# Group_5.net
KiCad netlist of a schematic drawn in EAGLE
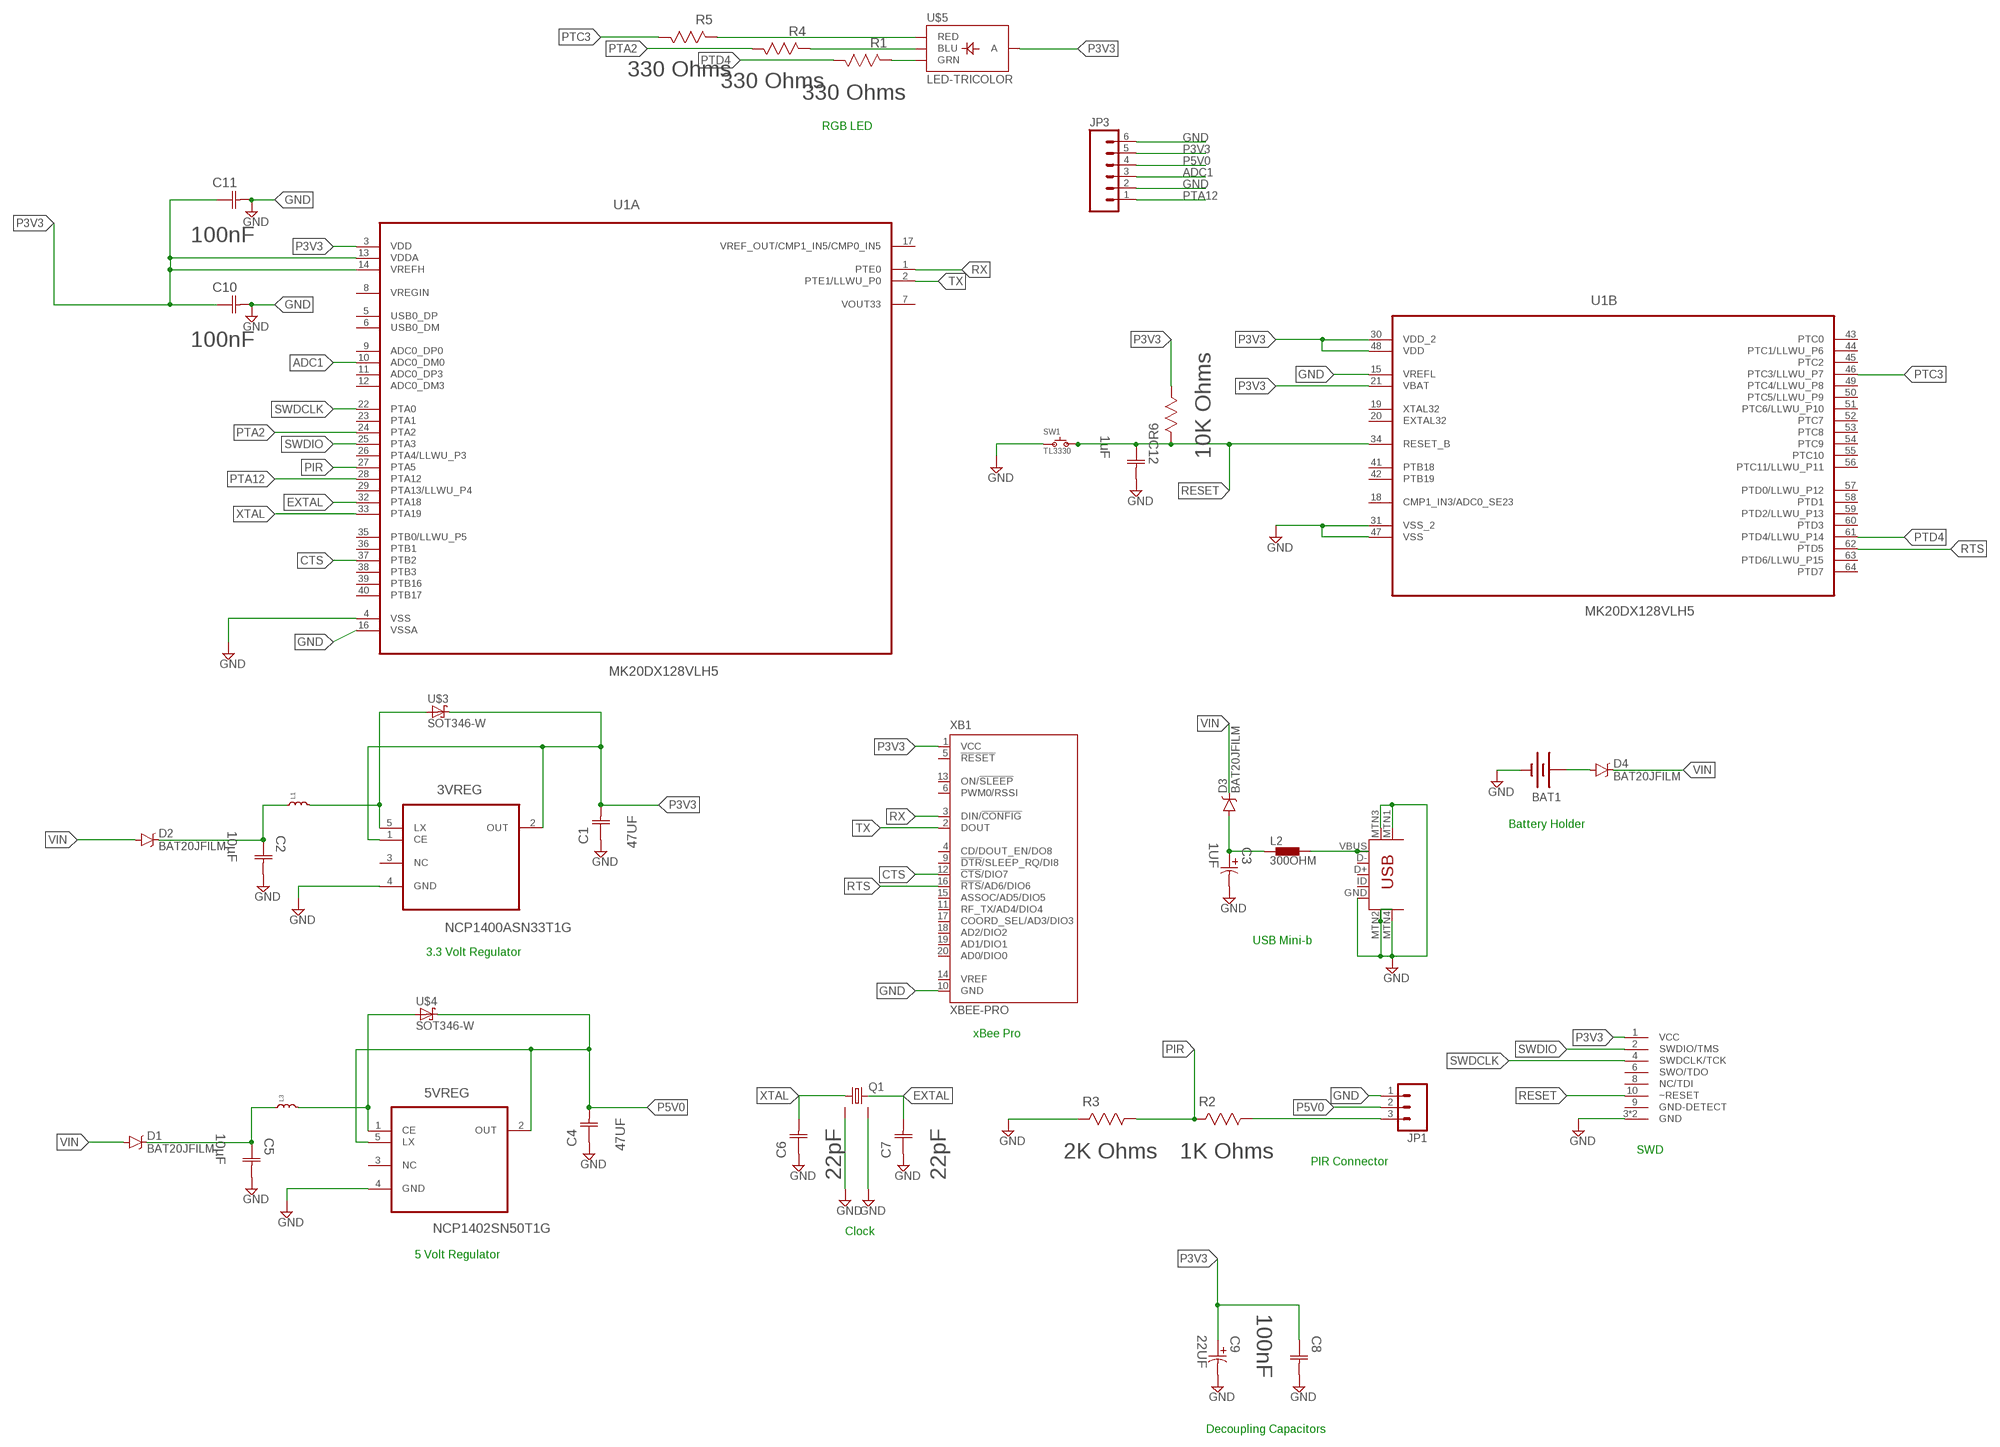
[diagram p0: schematic, sheet 1]

(export (version "E")
  (design (tool "Eeschema 10.0.6"))
  (components
    (comp (ref "3VREG")
      (value "NCP1400ASN33T1G")
      (footprint "eagle-import:SOT95P275X110-5N")
      (libsource (lib "eagle-import") (part "NCP1400ASN33T1G"))
    )
    (comp (ref "5VREG")
      (value "NCP1402SN50T1G")
      (footprint "eagle-import:SOT95P275X110-5N")
      (libsource (lib "eagle-import") (part "NCP1402SN50T1G"))
    )
    (comp (ref "BAT1")
      (value "BATTERY20PTH")
      (footprint "eagle-import:BATTCOM_20MM_PTH")
      (libsource (lib "eagle-import") (part "BATTERY20PTH"))
    )
    (comp (ref "C1")
      (value "47UF")
      (footprint "eagle-import:CAPCP6032X280N")
      (fields (field (name "MPN") "TPSC476M010R0350"))
      (libsource (lib "eagle-import") (part "TPSC476M010R0350"))
    )
    (comp (ref "C2")
      (value "10µF")
      (footprint "eagle-import:CAPCP6032X280N")
      (fields (field (name "MPN") "TAJC106M020R"))
      (libsource (lib "eagle-import") (part "TAJC106M020R"))
    )
    (comp (ref "C3")
      (value "1UF")
      (footprint "eagle-import:CAPAE430X610N")
      (fields (field (name "MPN") "EEE-1HA010SR") (field (name "TOLERANCE") " 20%"))
      (libsource (lib "eagle-import") (part "EEE--CASE-B1HA010SR"))
    )
    (comp (ref "C4")
      (value "47UF")
      (footprint "eagle-import:CAPCP6032X280N")
      (fields (field (name "MPN") "TPSC476M010R0350"))
      (libsource (lib "eagle-import") (part "TPSC476M010R0350"))
    )
    (comp (ref "C5")
      (value "10µF")
      (footprint "eagle-import:CAPCP6032X280N")
      (fields (field (name "MPN") "TAJC106M020R"))
      (libsource (lib "eagle-import") (part "TAJC106M020R"))
    )
    (comp (ref "C6")
      (value "22pF")
      (footprint "eagle-import:CAPC1608X85N")
      (fields (field (name "MPN") "C0603C220J5GACTU") (field (name "TOLERANCE") "±5%"))
      (libsource (lib "eagle-import") (part "C0603C220J5GACTU"))
    )
    (comp (ref "C7")
      (value "22pF")
      (footprint "eagle-import:CAPC1608X85N")
      (fields (field (name "MPN") "C0603C220J5GACTU") (field (name "TOLERANCE") "±5%"))
      (libsource (lib "eagle-import") (part "C0603C220J5GACTU"))
    )
    (comp (ref "C8")
      (value "100nF")
      (footprint "eagle-import:CAPC2013X95N")
      (fields (field (name "MPN") "CC0805KRX7R9BB104") (field (name "TOLERANCE") "±10%"))
      (libsource (lib "eagle-import") (part "CC0805KRX7R9BB104"))
    )
    (comp (ref "C9")
      (value "22UF")
      (footprint "eagle-import:CAPAE430X610N")
      (fields (field (name "MPN") "EEE-FT1V220AR") (field (name "TOLERANCE") "±20 %"))
      (libsource (lib "eagle-import") (part "EEE--CASE-BFT1V220AR"))
    )
    (comp (ref "C10")
      (value "100nF")
      (footprint "eagle-import:CAPC2013X95N")
      (fields (field (name "MPN") "CC0805KRX7R9BB104") (field (name "TOLERANCE") "±10%"))
      (libsource (lib "eagle-import") (part "CC0805KRX7R9BB104"))
    )
    (comp (ref "C11")
      (value "100nF")
      (footprint "eagle-import:CAPC2013X95N")
      (fields (field (name "MPN") "CC0805KRX7R9BB104") (field (name "TOLERANCE") "±10%"))
      (libsource (lib "eagle-import") (part "CC0805KRX7R9BB104"))
    )
    (comp (ref "C12")
      (value "1uF")
      (footprint "eagle-import:CAPC1608X94N")
      (fields (field (name "MPN") "0603YC105KAT2A") (field (name "TOLERANCE") "±10%"))
      (libsource (lib "eagle-import") (part "0603YC105KAT2A"))
    )
    (comp (ref "D1")
      (value "BAT20JFILM")
      (footprint "eagle-import:SOD-323")
      (libsource (lib "eagle-import") (part "BAT20JFILM"))
    )
    (comp (ref "D2")
      (value "BAT20JFILM")
      (footprint "eagle-import:SOD-323")
      (libsource (lib "eagle-import") (part "BAT20JFILM"))
    )
    (comp (ref "D3")
      (value "BAT20JFILM")
      (footprint "eagle-import:SOD-323")
      (libsource (lib "eagle-import") (part "BAT20JFILM"))
    )
    (comp (ref "D4")
      (value "BAT20JFILM")
      (footprint "eagle-import:SOD-323")
      (libsource (lib "eagle-import") (part "BAT20JFILM"))
    )
    (comp (ref "JP1")
      (value "M03PTH")
      (footprint "eagle-import:1X03")
      (libsource (lib "eagle-import") (part "M03PTH"))
    )
    (comp (ref "JP3")
      (value "M06LONGPADS")
      (footprint "eagle-import:1X06_LONGPADS")
      (libsource (lib "eagle-import") (part "M06LONGPADS"))
    )
    (comp (ref "L1")
      (value "INDUCTOR-SDR0403")
      (footprint "eagle-import:SDR0403")
      (libsource (lib "eagle-import") (part "INDUCTOR-SDR0403"))
    )
    (comp (ref "L2")
      (value "300OHM")
      (footprint "eagle-import:0402")
      (libsource (lib "eagle-import") (part "BLM15HB121SN1"))
    )
    (comp (ref "L3")
      (value "INDUCTOR-SDR0403")
      (footprint "eagle-import:SDR0403")
      (libsource (lib "eagle-import") (part "INDUCTOR-SDR0403"))
    )
    (comp (ref "Q1")
      (value "CRYSTALCTS406")
      (footprint "eagle-import:CTS406")
      (libsource (lib "eagle-import") (part "CRYSTALCTS406"))
    )
    (comp (ref "R1")
      (value "330 Ohms")
      (footprint "eagle-import:RESC2013X65N")
      (fields (field (name "MPN") "MC0.1W08051%330R") (field (name "TOLERANCE") "±1%"))
      (libsource (lib "eagle-import") (part "MC0.1W08051%330R"))
    )
    (comp (ref "R2")
      (value "1K Ohms")
      (footprint "eagle-import:RESC3216X71N")
      (fields (field (name "MPN") "MC0.125W12061%1K") (field (name "TOLERANCE") "±1%"))
      (libsource (lib "eagle-import") (part "MC0.125W12061%1K"))
    )
    (comp (ref "R3")
      (value "2K Ohms")
      (footprint "eagle-import:RESC3216X71N")
      (fields (field (name "MPN") "MC0.125W12061%2K") (field (name "TOLERANCE") "±1%"))
      (libsource (lib "eagle-import") (part "MC0.125W12061%2K"))
    )
    (comp (ref "R4")
      (value "330 Ohms")
      (footprint "eagle-import:RESC2013X65N")
      (fields (field (name "MPN") "MC0.1W08051%330R") (field (name "TOLERANCE") "±1%"))
      (libsource (lib "eagle-import") (part "MC0.1W08051%330R"))
    )
    (comp (ref "R5")
      (value "330 Ohms")
      (footprint "eagle-import:RESC2013X65N")
      (fields (field (name "MPN") "MC0.1W08051%330R") (field (name "TOLERANCE") "±1%"))
      (libsource (lib "eagle-import") (part "MC0.1W08051%330R"))
    )
    (comp (ref "R6")
      (value "10K Ohms")
      (footprint "eagle-import:RESC1608X60N")
      (fields (field (name "MPN") "MC0.063W06035%10K") (field (name "TOLERANCE") "±1%"))
      (libsource (lib "eagle-import") (part "MC0.063W06035%10K"))
    )
    (comp (ref "SW1")
      (value "TL3330")
      (footprint "eagle-import:TL3330")
      (libsource (lib "eagle-import") (part "TL3330"))
    )
    (comp (ref "U$1")
      (value "2X5_0.05\"_CORTEX_DEBUGTH_NOKEY_UNSHROUDED")
      (footprint "eagle-import:2X5_0.05__TH_NS")
      (libsource (lib "eagle-import") (part "2X5_0.05{dblquote}_CORTEX_DEBUGTH_NOKEY_UNSHROUDED"))
    )
    (comp (ref "U$2")
      (value "USB-MINIB-5PIN")
      (footprint "eagle-import:USB-MINIB")
      (libsource (lib "eagle-import") (part "USB-MINIB-5PIN"))
    )
    (comp (ref "U$3")
      (value "SOT346-W")
      (footprint "eagle-import:SOT346-W")
      (libsource (lib "eagle-import") (part "SOT346-W"))
    )
    (comp (ref "U$4")
      (value "SOT346-W")
      (footprint "eagle-import:SOT346-W")
      (libsource (lib "eagle-import") (part "SOT346-W"))
    )
    (comp (ref "U$5")
      (value "LED-TRICOLOR")
      (footprint "eagle-import:LED-TRICOLOR-SMD")
      (libsource (lib "eagle-import") (part "LED-TRICOLOR"))
    )
    (comp (ref "U1")
      (value "MK20DX128VLH5")
      (footprint "eagle-import:QFP50P1200X1200X160-64N")
      (libsource (lib "eagle-import") (part "MK20DX128VLH5"))
    )
    (comp (ref "XB1")
      (value "XBEE-PRO")
      (footprint "eagle-import:XBEE-PRO")
      (fields (field (name "MPN") "XBP24-AWI-001"))
      (libsource (lib "eagle-import") (part "XBEE-PRO"))
    )
  )
  (nets
    (net (code "1") (name "ADC1") (class "Default")
      (node (ref "JP3") (pin "3") (pinfunction "3_3") (pintype "passive"))
      (node (ref "U1") (pin "10") (pinfunction "ADC0_DM0_10") (pintype "passive"))
    )
    (net (code "2") (name "CTS") (class "Default")
      (node (ref "U1") (pin "37") (pinfunction "PTB2_37") (pintype "bidirectional"))
      (node (ref "XB1") (pin "12") (pinfunction "~{CTS}/DIO7_12") (pintype "bidirectional"))
    )
    (net (code "3") (name "EXTAL") (class "Default")
      (node (ref "C7") (pin "2") (pinfunction "C2_2") (pintype "passive"))
      (node (ref "Q1") (pin "3") (pinfunction "2_3") (pintype "passive"))
      (node (ref "U1") (pin "32") (pinfunction "PTA18_32") (pintype "bidirectional"))
    )
    (net (code "4") (name "GND") (class "Default")
      (node (ref "3VREG") (pin "4") (pinfunction "GND_4") (pintype "passive"))
      (node (ref "5VREG") (pin "4") (pinfunction "GND_4") (pintype "passive"))
      (node (ref "BAT1") (pin "2") (pinfunction "-_2") (pintype "power_in"))
      (node (ref "C1") (pin "1") (pinfunction "C1_1") (pintype "passive"))
      (node (ref "C10") (pin "2") (pinfunction "C2_2") (pintype "passive"))
      (node (ref "C11") (pin "2") (pinfunction "C2_2") (pintype "passive"))
      (node (ref "C12") (pin "2") (pinfunction "C2_2") (pintype "passive"))
      (node (ref "C2") (pin "2") (pinfunction "C2_2") (pintype "passive"))
      (node (ref "C3") (pin "2") (pinfunction "2_2") (pintype "passive"))
      (node (ref "C4") (pin "1") (pinfunction "C1_1") (pintype "passive"))
      (node (ref "C5") (pin "2") (pinfunction "C2_2") (pintype "passive"))
      (node (ref "C6") (pin "1") (pinfunction "C1_1") (pintype "passive"))
      (node (ref "C7") (pin "1") (pinfunction "C1_1") (pintype "passive"))
      (node (ref "C8") (pin "2") (pinfunction "C2_2") (pintype "passive"))
      (node (ref "C9") (pin "2") (pinfunction "2_2") (pintype "passive"))
      (node (ref "JP1") (pin "1") (pinfunction "1_1") (pintype "passive"))
      (node (ref "JP3") (pin "2") (pinfunction "2_2") (pintype "passive"))
      (node (ref "JP3") (pin "6") (pinfunction "6_6") (pintype "passive"))
      (node (ref "Q1") (pin "2") (pinfunction "GND1_2") (pintype "passive"))
      (node (ref "Q1") (pin "4") (pinfunction "GND2_4") (pintype "passive"))
      (node (ref "R3") (pin "2") (pinfunction "R2_2") (pintype "passive"))
      (node (ref "SW1") (pin "1") (pinfunction "1_1") (pintype "bidirectional"))
      (node (ref "U$1") (pin "3") (pinfunction "GND_3") (pintype "bidirectional"))
      (node (ref "U$1") (pin "5") (pinfunction "GND_5") (pintype "bidirectional"))
      (node (ref "U$2") (pin "GND") (pinfunction "GND_GND") (pintype "bidirectional"))
      (node (ref "U$2") (pin "MTN1") (pinfunction "MTN2_MTN1") (pintype "bidirectional"))
      (node (ref "U$2") (pin "MTN2") (pinfunction "MTN3_MTN2") (pintype "bidirectional"))
      (node (ref "U$2") (pin "MTN3") (pinfunction "MTN1_MTN3") (pintype "bidirectional"))
      (node (ref "U$2") (pin "MTN4") (pinfunction "MTN4_MTN4") (pintype "bidirectional"))
      (node (ref "U1") (pin "15") (pinfunction "VREFL_15") (pintype "passive"))
      (node (ref "U1") (pin "16") (pinfunction "VSSA_16") (pintype "passive"))
      (node (ref "U1") (pin "31") (pinfunction "VSS_2_31") (pintype "passive"))
      (node (ref "U1") (pin "4") (pinfunction "VSS_4") (pintype "passive"))
      (node (ref "U1") (pin "47") (pinfunction "VSS_47") (pintype "passive"))
      (node (ref "XB1") (pin "10") (pinfunction "GND_10") (pintype "power_in"))
    )
    (net (code "5") (name "Net-(3VREG-LX)") (class "Default")
      (node (ref "3VREG") (pin "5") (pinfunction "LX_5") (pintype "input"))
      (node (ref "L1") (pin "2") (pinfunction "2_2") (pintype "passive"))
      (node (ref "U$3") (pin "1") (pinfunction "A_1") (pintype "passive"))
    )
    (net (code "6") (name "Net-(5VREG-CE)") (class "Default")
      (node (ref "5VREG") (pin "1") (pinfunction "CE_1") (pintype "input"))
      (node (ref "L3") (pin "2") (pinfunction "2_2") (pintype "passive"))
      (node (ref "U$4") (pin "1") (pinfunction "A_1") (pintype "passive"))
    )
    (net (code "7") (name "Net-(BAT1-+)") (class "Default")
      (node (ref "BAT1") (pin "1") (pinfunction "+_1") (pintype "power_in"))
      (node (ref "D4") (pin "A") (pinfunction "A_A") (pintype "passive"))
    )
    (net (code "8") (name "Net-(C2-C1)") (class "Default")
      (node (ref "C2") (pin "1") (pinfunction "C1_1") (pintype "passive"))
      (node (ref "D2") (pin "C") (pinfunction "C_C") (pintype "passive"))
      (node (ref "L1") (pin "1") (pinfunction "1_1") (pintype "passive"))
    )
    (net (code "9") (name "Net-(C3-Pad1)") (class "Default")
      (node (ref "C3") (pin "1") (pinfunction "1_1") (pintype "passive"))
      (node (ref "D3") (pin "A") (pinfunction "A_A") (pintype "passive"))
      (node (ref "L2") (pin "1") (pinfunction "1_1") (pintype "passive"))
    )
    (net (code "10") (name "Net-(C5-C1)") (class "Default")
      (node (ref "C5") (pin "1") (pinfunction "C1_1") (pintype "passive"))
      (node (ref "D1") (pin "C") (pinfunction "C_C") (pintype "passive"))
      (node (ref "L3") (pin "1") (pinfunction "1_1") (pintype "passive"))
    )
    (net (code "11") (name "Net-(L2-Pad2)") (class "Default")
      (node (ref "L2") (pin "2") (pinfunction "2_2") (pintype "passive"))
      (node (ref "U$2") (pin "VBUS") (pinfunction "VBUS_VBUS") (pintype "bidirectional"))
    )
    (net (code "12") (name "Net-(R1-R2)") (class "Default")
      (node (ref "R1") (pin "2") (pinfunction "R2_2") (pintype "passive"))
      (node (ref "U$5") (pin "G") (pinfunction "GRN_G") (pintype "bidirectional"))
    )
    (net (code "13") (name "Net-(R2-R1)") (class "Default")
      (node (ref "JP1") (pin "3") (pinfunction "3_3") (pintype "passive"))
      (node (ref "R2") (pin "1") (pinfunction "R1_1") (pintype "passive"))
    )
    (net (code "14") (name "Net-(R4-R2)") (class "Default")
      (node (ref "R4") (pin "2") (pinfunction "R2_2") (pintype "passive"))
      (node (ref "U$5") (pin "B") (pinfunction "BLU_B") (pintype "bidirectional"))
    )
    (net (code "15") (name "Net-(R5-R2)") (class "Default")
      (node (ref "R5") (pin "2") (pinfunction "R2_2") (pintype "passive"))
      (node (ref "U$5") (pin "R") (pinfunction "RED_R") (pintype "bidirectional"))
    )
    (net (code "16") (name "P3V3") (class "Default")
      (node (ref "3VREG") (pin "1") (pinfunction "CE_1") (pintype "input"))
      (node (ref "3VREG") (pin "2") (pinfunction "OUT_2") (pintype "output"))
      (node (ref "C1") (pin "2") (pinfunction "C2_2") (pintype "passive"))
      (node (ref "C10") (pin "1") (pinfunction "C1_1") (pintype "passive"))
      (node (ref "C11") (pin "1") (pinfunction "C1_1") (pintype "passive"))
      (node (ref "C8") (pin "1") (pinfunction "C1_1") (pintype "passive"))
      (node (ref "C9") (pin "1") (pinfunction "1_1") (pintype "passive"))
      (node (ref "JP3") (pin "5") (pinfunction "5_5") (pintype "passive"))
      (node (ref "R6") (pin "1") (pinfunction "R1_1") (pintype "passive"))
      (node (ref "U$1") (pin "1") (pinfunction "VCC_1") (pintype "bidirectional"))
      (node (ref "U$3") (pin "3") (pinfunction "C_3") (pintype "passive"))
      (node (ref "U$5") (pin "A") (pinfunction "A_A") (pintype "bidirectional"))
      (node (ref "U1") (pin "13") (pinfunction "VDDA_13") (pintype "power_in"))
      (node (ref "U1") (pin "14") (pinfunction "VREFH_14") (pintype "passive"))
      (node (ref "U1") (pin "21") (pinfunction "VBAT_21") (pintype "power_in"))
      (node (ref "U1") (pin "3") (pinfunction "VDD_3") (pintype "power_in"))
      (node (ref "U1") (pin "30") (pinfunction "VDD_2_30") (pintype "power_in"))
      (node (ref "U1") (pin "48") (pinfunction "VDD_48") (pintype "power_in"))
      (node (ref "XB1") (pin "1") (pinfunction "VCC_1") (pintype "power_in"))
    )
    (net (code "17") (name "P5V0") (class "Default")
      (node (ref "5VREG") (pin "2") (pinfunction "OUT_2") (pintype "output"))
      (node (ref "5VREG") (pin "5") (pinfunction "LX_5") (pintype "input"))
      (node (ref "C4") (pin "2") (pinfunction "C2_2") (pintype "passive"))
      (node (ref "JP1") (pin "2") (pinfunction "2_2") (pintype "passive"))
      (node (ref "JP3") (pin "4") (pinfunction "4_4") (pintype "passive"))
      (node (ref "U$4") (pin "3") (pinfunction "C_3") (pintype "passive"))
    )
    (net (code "18") (name "PIR") (class "Default")
      (node (ref "R2") (pin "2") (pinfunction "R2_2") (pintype "passive"))
      (node (ref "R3") (pin "1") (pinfunction "R1_1") (pintype "passive"))
      (node (ref "U1") (pin "27") (pinfunction "PTA5_27") (pintype "bidirectional"))
    )
    (net (code "19") (name "PTA2") (class "Default")
      (node (ref "R4") (pin "1") (pinfunction "R1_1") (pintype "passive"))
      (node (ref "U1") (pin "24") (pinfunction "PTA2_24") (pintype "bidirectional"))
    )
    (net (code "20") (name "PTA12") (class "Default")
      (node (ref "JP3") (pin "1") (pinfunction "1_1") (pintype "passive"))
      (node (ref "U1") (pin "28") (pinfunction "PTA12_28") (pintype "bidirectional"))
    )
    (net (code "21") (name "PTC3") (class "Default")
      (node (ref "R5") (pin "1") (pinfunction "R1_1") (pintype "passive"))
      (node (ref "U1") (pin "46") (pinfunction "PTC3/LLWU_P7_46") (pintype "bidirectional"))
    )
    (net (code "22") (name "PTD4") (class "Default")
      (node (ref "R1") (pin "1") (pinfunction "R1_1") (pintype "passive"))
      (node (ref "U1") (pin "61") (pinfunction "PTD4/LLWU_P14_61") (pintype "bidirectional"))
    )
    (net (code "23") (name "RESET") (class "Default")
      (node (ref "C12") (pin "1") (pinfunction "C1_1") (pintype "passive"))
      (node (ref "R6") (pin "2") (pinfunction "R2_2") (pintype "passive"))
      (node (ref "SW1") (pin "2") (pinfunction "2_2") (pintype "bidirectional"))
      (node (ref "U$1") (pin "10") (pinfunction "~{RESET}_10") (pintype "bidirectional"))
      (node (ref "U1") (pin "34") (pinfunction "RESET_B_34") (pintype "passive"))
    )
    (net (code "24") (name "RTS") (class "Default")
      (node (ref "U1") (pin "62") (pinfunction "PTD5_62") (pintype "bidirectional"))
      (node (ref "XB1") (pin "16") (pinfunction "~{RTS}/AD6/DIO6_16") (pintype "bidirectional"))
    )
    (net (code "25") (name "RX") (class "Default")
      (node (ref "U1") (pin "1") (pinfunction "PTE0_1") (pintype "bidirectional"))
      (node (ref "XB1") (pin "3") (pinfunction "DIN/~{CONFIG}_3") (pintype "input"))
    )
    (net (code "26") (name "SWDCLK") (class "Default")
      (node (ref "U$1") (pin "4") (pinfunction "SWDCLK/TCK_4") (pintype "bidirectional"))
      (node (ref "U1") (pin "22") (pinfunction "PTA0_22") (pintype "bidirectional"))
    )
    (net (code "27") (name "SWDIO") (class "Default")
      (node (ref "U$1") (pin "2") (pinfunction "SWDIO/TMS_2") (pintype "bidirectional"))
      (node (ref "U1") (pin "25") (pinfunction "PTA3_25") (pintype "bidirectional"))
    )
    (net (code "28") (name "TX") (class "Default")
      (node (ref "U1") (pin "2") (pinfunction "PTE1/LLWU_P0_2") (pintype "bidirectional"))
      (node (ref "XB1") (pin "2") (pinfunction "DOUT_2") (pintype "output"))
    )
    (net (code "29") (name "VIN") (class "Default")
      (node (ref "D1") (pin "A") (pinfunction "A_A") (pintype "passive"))
      (node (ref "D2") (pin "A") (pinfunction "A_A") (pintype "passive"))
      (node (ref "D3") (pin "C") (pinfunction "C_C") (pintype "passive"))
      (node (ref "D4") (pin "C") (pinfunction "C_C") (pintype "passive"))
    )
    (net (code "30") (name "XTAL") (class "Default")
      (node (ref "C6") (pin "2") (pinfunction "C2_2") (pintype "passive"))
      (node (ref "Q1") (pin "1") (pinfunction "1_1") (pintype "passive"))
      (node (ref "U1") (pin "33") (pinfunction "PTA19_33") (pintype "bidirectional"))
    )
    (net (code "31") (name "unconnected-(3VREG-NC-Pad3)") (class "Default")
      (node (ref "3VREG") (pin "3") (pinfunction "NC_3") (pintype "no_connect"))
    )
    (net (code "32") (name "unconnected-(5VREG-NC-Pad3)") (class "Default")
      (node (ref "5VREG") (pin "3") (pinfunction "NC_3") (pintype "no_connect"))
    )
    (net (code "33") (name "unconnected-(U$1-GND-DETECT-Pad9)") (class "Default")
      (node (ref "U$1") (pin "9") (pinfunction "GND-DETECT_9") (pintype "bidirectional"))
    )
    (net (code "34") (name "unconnected-(U$1-NC{slash}TDI-Pad8)") (class "Default")
      (node (ref "U$1") (pin "8") (pinfunction "NC/TDI_8") (pintype "bidirectional"))
    )
    (net (code "35") (name "unconnected-(U$1-SWO{slash}TDO-Pad6)") (class "Default")
      (node (ref "U$1") (pin "6") (pinfunction "SWO/TDO_6") (pintype "bidirectional"))
    )
    (net (code "36") (name "unconnected-(U$2-PadD+)") (class "Default")
      (node (ref "U$2") (pin "D+") (pinfunction "D+_D+") (pintype "bidirectional"))
    )
    (net (code "37") (name "unconnected-(U$2-PadD-)") (class "Default")
      (node (ref "U$2") (pin "D-") (pinfunction "D-_D-") (pintype "bidirectional"))
    )
    (net (code "38") (name "unconnected-(U$2-PadID)") (class "Default")
      (node (ref "U$2") (pin "ID") (pinfunction "ID_ID") (pintype "bidirectional"))
    )
    (net (code "39") (name "unconnected-(U1A-ADC0_DM3-Pad12)") (class "Default")
      (node (ref "U1") (pin "12") (pinfunction "ADC0_DM3_12") (pintype "passive"))
    )
    (net (code "40") (name "unconnected-(U1A-ADC0_DP0-Pad9)") (class "Default")
      (node (ref "U1") (pin "9") (pinfunction "ADC0_DP0_9") (pintype "passive"))
    )
    (net (code "41") (name "unconnected-(U1A-ADC0_DP3-Pad11)") (class "Default")
      (node (ref "U1") (pin "11") (pinfunction "ADC0_DP3_11") (pintype "passive"))
    )
    (net (code "42") (name "unconnected-(U1A-PTA1-Pad23)") (class "Default")
      (node (ref "U1") (pin "23") (pinfunction "PTA1_23") (pintype "bidirectional"))
    )
    (net (code "43") (name "unconnected-(U1A-PTA4{slash}LLWU_P3-Pad26)") (class "Default")
      (node (ref "U1") (pin "26") (pinfunction "PTA4/LLWU_P3_26") (pintype "bidirectional"))
    )
    (net (code "44") (name "unconnected-(U1A-PTA13{slash}LLWU_P4-Pad29)") (class "Default")
      (node (ref "U1") (pin "29") (pinfunction "PTA13/LLWU_P4_29") (pintype "bidirectional"))
    )
    (net (code "45") (name "unconnected-(U1A-PTB0{slash}LLWU_P5-Pad35)") (class "Default")
      (node (ref "U1") (pin "35") (pinfunction "PTB0/LLWU_P5_35") (pintype "bidirectional"))
    )
    (net (code "46") (name "unconnected-(U1A-PTB1-Pad36)") (class "Default")
      (node (ref "U1") (pin "36") (pinfunction "PTB1_36") (pintype "bidirectional"))
    )
    (net (code "47") (name "unconnected-(U1A-PTB3-Pad38)") (class "Default")
      (node (ref "U1") (pin "38") (pinfunction "PTB3_38") (pintype "bidirectional"))
    )
    (net (code "48") (name "unconnected-(U1A-PTB16-Pad39)") (class "Default")
      (node (ref "U1") (pin "39") (pinfunction "PTB16_39") (pintype "bidirectional"))
    )
    (net (code "49") (name "unconnected-(U1A-PTB17-Pad40)") (class "Default")
      (node (ref "U1") (pin "40") (pinfunction "PTB17_40") (pintype "bidirectional"))
    )
    (net (code "50") (name "unconnected-(U1A-USB0_DM-Pad6)") (class "Default")
      (node (ref "U1") (pin "6") (pinfunction "USB0_DM_6") (pintype "passive"))
    )
    (net (code "51") (name "unconnected-(U1A-USB0_DP-Pad5)") (class "Default")
      (node (ref "U1") (pin "5") (pinfunction "USB0_DP_5") (pintype "passive"))
    )
    (net (code "52") (name "unconnected-(U1A-VOUT33-Pad7)") (class "Default")
      (node (ref "U1") (pin "7") (pinfunction "VOUT33_7") (pintype "output"))
    )
    (net (code "53") (name "unconnected-(U1A-VREF_OUT{slash}CMP1_IN5{slash}CMP0_IN5-Pad17)") (class "Default")
      (node (ref "U1") (pin "17") (pinfunction "VREF_OUT/CMP1_IN5/CMP0_IN5_17") (pintype "output"))
    )
    (net (code "54") (name "unconnected-(U1A-VREGIN-Pad8)") (class "Default")
      (node (ref "U1") (pin "8") (pinfunction "VREGIN_8") (pintype "input"))
    )
    (net (code "55") (name "unconnected-(U1B-CMP1_IN3{slash}ADC0_SE23-Pad18)") (class "Default")
      (node (ref "U1") (pin "18") (pinfunction "CMP1_IN3/ADC0_SE23_18") (pintype "passive"))
    )
    (net (code "56") (name "unconnected-(U1B-EXTAL32-Pad20)") (class "Default")
      (node (ref "U1") (pin "20") (pinfunction "EXTAL32_20") (pintype "passive"))
    )
    (net (code "57") (name "unconnected-(U1B-PTB18-Pad41)") (class "Default")
      (node (ref "U1") (pin "41") (pinfunction "PTB18_41") (pintype "bidirectional"))
    )
    (net (code "58") (name "unconnected-(U1B-PTB19-Pad42)") (class "Default")
      (node (ref "U1") (pin "42") (pinfunction "PTB19_42") (pintype "bidirectional"))
    )
    (net (code "59") (name "unconnected-(U1B-PTC0-Pad43)") (class "Default")
      (node (ref "U1") (pin "43") (pinfunction "PTC0_43") (pintype "bidirectional"))
    )
    (net (code "60") (name "unconnected-(U1B-PTC1{slash}LLWU_P6-Pad44)") (class "Default")
      (node (ref "U1") (pin "44") (pinfunction "PTC1/LLWU_P6_44") (pintype "bidirectional"))
    )
    (net (code "61") (name "unconnected-(U1B-PTC2-Pad45)") (class "Default")
      (node (ref "U1") (pin "45") (pinfunction "PTC2_45") (pintype "bidirectional"))
    )
    (net (code "62") (name "unconnected-(U1B-PTC4{slash}LLWU_P8-Pad49)") (class "Default")
      (node (ref "U1") (pin "49") (pinfunction "PTC4/LLWU_P8_49") (pintype "bidirectional"))
    )
    (net (code "63") (name "unconnected-(U1B-PTC5{slash}LLWU_P9-Pad50)") (class "Default")
      (node (ref "U1") (pin "50") (pinfunction "PTC5/LLWU_P9_50") (pintype "bidirectional"))
    )
    (net (code "64") (name "unconnected-(U1B-PTC6{slash}LLWU_P10-Pad51)") (class "Default")
      (node (ref "U1") (pin "51") (pinfunction "PTC6/LLWU_P10_51") (pintype "bidirectional"))
    )
    (net (code "65") (name "unconnected-(U1B-PTC7-Pad52)") (class "Default")
      (node (ref "U1") (pin "52") (pinfunction "PTC7_52") (pintype "bidirectional"))
    )
    (net (code "66") (name "unconnected-(U1B-PTC8-Pad53)") (class "Default")
      (node (ref "U1") (pin "53") (pinfunction "PTC8_53") (pintype "bidirectional"))
    )
    (net (code "67") (name "unconnected-(U1B-PTC9-Pad54)") (class "Default")
      (node (ref "U1") (pin "54") (pinfunction "PTC9_54") (pintype "bidirectional"))
    )
    (net (code "68") (name "unconnected-(U1B-PTC10-Pad55)") (class "Default")
      (node (ref "U1") (pin "55") (pinfunction "PTC10_55") (pintype "bidirectional"))
    )
    (net (code "69") (name "unconnected-(U1B-PTC11{slash}LLWU_P11-Pad56)") (class "Default")
      (node (ref "U1") (pin "56") (pinfunction "PTC11/LLWU_P11_56") (pintype "bidirectional"))
    )
    (net (code "70") (name "unconnected-(U1B-PTD0{slash}LLWU_P12-Pad57)") (class "Default")
      (node (ref "U1") (pin "57") (pinfunction "PTD0/LLWU_P12_57") (pintype "bidirectional"))
    )
    (net (code "71") (name "unconnected-(U1B-PTD1-Pad58)") (class "Default")
      (node (ref "U1") (pin "58") (pinfunction "PTD1_58") (pintype "bidirectional"))
    )
    (net (code "72") (name "unconnected-(U1B-PTD2{slash}LLWU_P13-Pad59)") (class "Default")
      (node (ref "U1") (pin "59") (pinfunction "PTD2/LLWU_P13_59") (pintype "bidirectional"))
    )
    (net (code "73") (name "unconnected-(U1B-PTD3-Pad60)") (class "Default")
      (node (ref "U1") (pin "60") (pinfunction "PTD3_60") (pintype "bidirectional"))
    )
    (net (code "74") (name "unconnected-(U1B-PTD6{slash}LLWU_P15-Pad63)") (class "Default")
      (node (ref "U1") (pin "63") (pinfunction "PTD6/LLWU_P15_63") (pintype "bidirectional"))
    )
    (net (code "75") (name "unconnected-(U1B-PTD7-Pad64)") (class "Default")
      (node (ref "U1") (pin "64") (pinfunction "PTD7_64") (pintype "bidirectional"))
    )
    (net (code "76") (name "unconnected-(U1B-XTAL32-Pad19)") (class "Default")
      (node (ref "U1") (pin "19") (pinfunction "XTAL32_19") (pintype "passive"))
    )
    (net (code "77") (name "unconnected-(XB1-AD0{slash}DIO0-Pad20)") (class "Default")
      (node (ref "XB1") (pin "20") (pinfunction "AD0/DIO0_20") (pintype "bidirectional"))
    )
    (net (code "78") (name "unconnected-(XB1-AD1{slash}DIO1-Pad19)") (class "Default")
      (node (ref "XB1") (pin "19") (pinfunction "AD1/DIO1_19") (pintype "bidirectional"))
    )
    (net (code "79") (name "unconnected-(XB1-AD2{slash}DIO2-Pad18)") (class "Default")
      (node (ref "XB1") (pin "18") (pinfunction "AD2/DIO2_18") (pintype "bidirectional"))
    )
    (net (code "80") (name "unconnected-(XB1-ASSOC{slash}AD5{slash}DIO5-Pad15)") (class "Default")
      (node (ref "XB1") (pin "15") (pinfunction "ASSOC/AD5/DIO5_15") (pintype "bidirectional"))
    )
    (net (code "81") (name "unconnected-(XB1-CD{slash}DOUT_EN{slash}DO8-Pad4)") (class "Default")
      (node (ref "XB1") (pin "4") (pinfunction "CD/DOUT_EN/DO8_4") (pintype "output"))
    )
    (net (code "82") (name "unconnected-(XB1-COORD_SEL{slash}AD3{slash}DIO3-Pad17)") (class "Default")
      (node (ref "XB1") (pin "17") (pinfunction "COORD_SEL/AD3/DIO3_17") (pintype "bidirectional"))
    )
    (net (code "83") (name "unconnected-(XB1-ON{slash}~{SLEEP}-Pad13)") (class "Default")
      (node (ref "XB1") (pin "13") (pinfunction "ON/~{SLEEP}_13") (pintype "output"))
    )
    (net (code "84") (name "unconnected-(XB1-PWM0{slash}RSSI-Pad6)") (class "Default")
      (node (ref "XB1") (pin "6") (pinfunction "PWM0/RSSI_6") (pintype "output"))
    )
    (net (code "85") (name "unconnected-(XB1-RF_TX{slash}AD4{slash}DIO4-Pad11)") (class "Default")
      (node (ref "XB1") (pin "11") (pinfunction "RF_TX/AD4/DIO4_11") (pintype "bidirectional"))
    )
    (net (code "86") (name "unconnected-(XB1-VREF-Pad14)") (class "Default")
      (node (ref "XB1") (pin "14") (pinfunction "VREF_14") (pintype "input"))
    )
    (net (code "87") (name "unconnected-(XB1-~{DTR}{slash}SLEEP_RQ{slash}DI8-Pad9)") (class "Default")
      (node (ref "XB1") (pin "9") (pinfunction "~{DTR}/SLEEP_RQ/DI8_9") (pintype "bidirectional"))
    )
    (net (code "88") (name "unconnected-(XB1-~{RESET}-Pad5)") (class "Default")
      (node (ref "XB1") (pin "5") (pinfunction "~{RESET}_5") (pintype "input"))
    )
  )
)
